# 12_LPDDR2-32_168_BGA134.net
KiCad netlist of a schematic drawn in Altium Designer
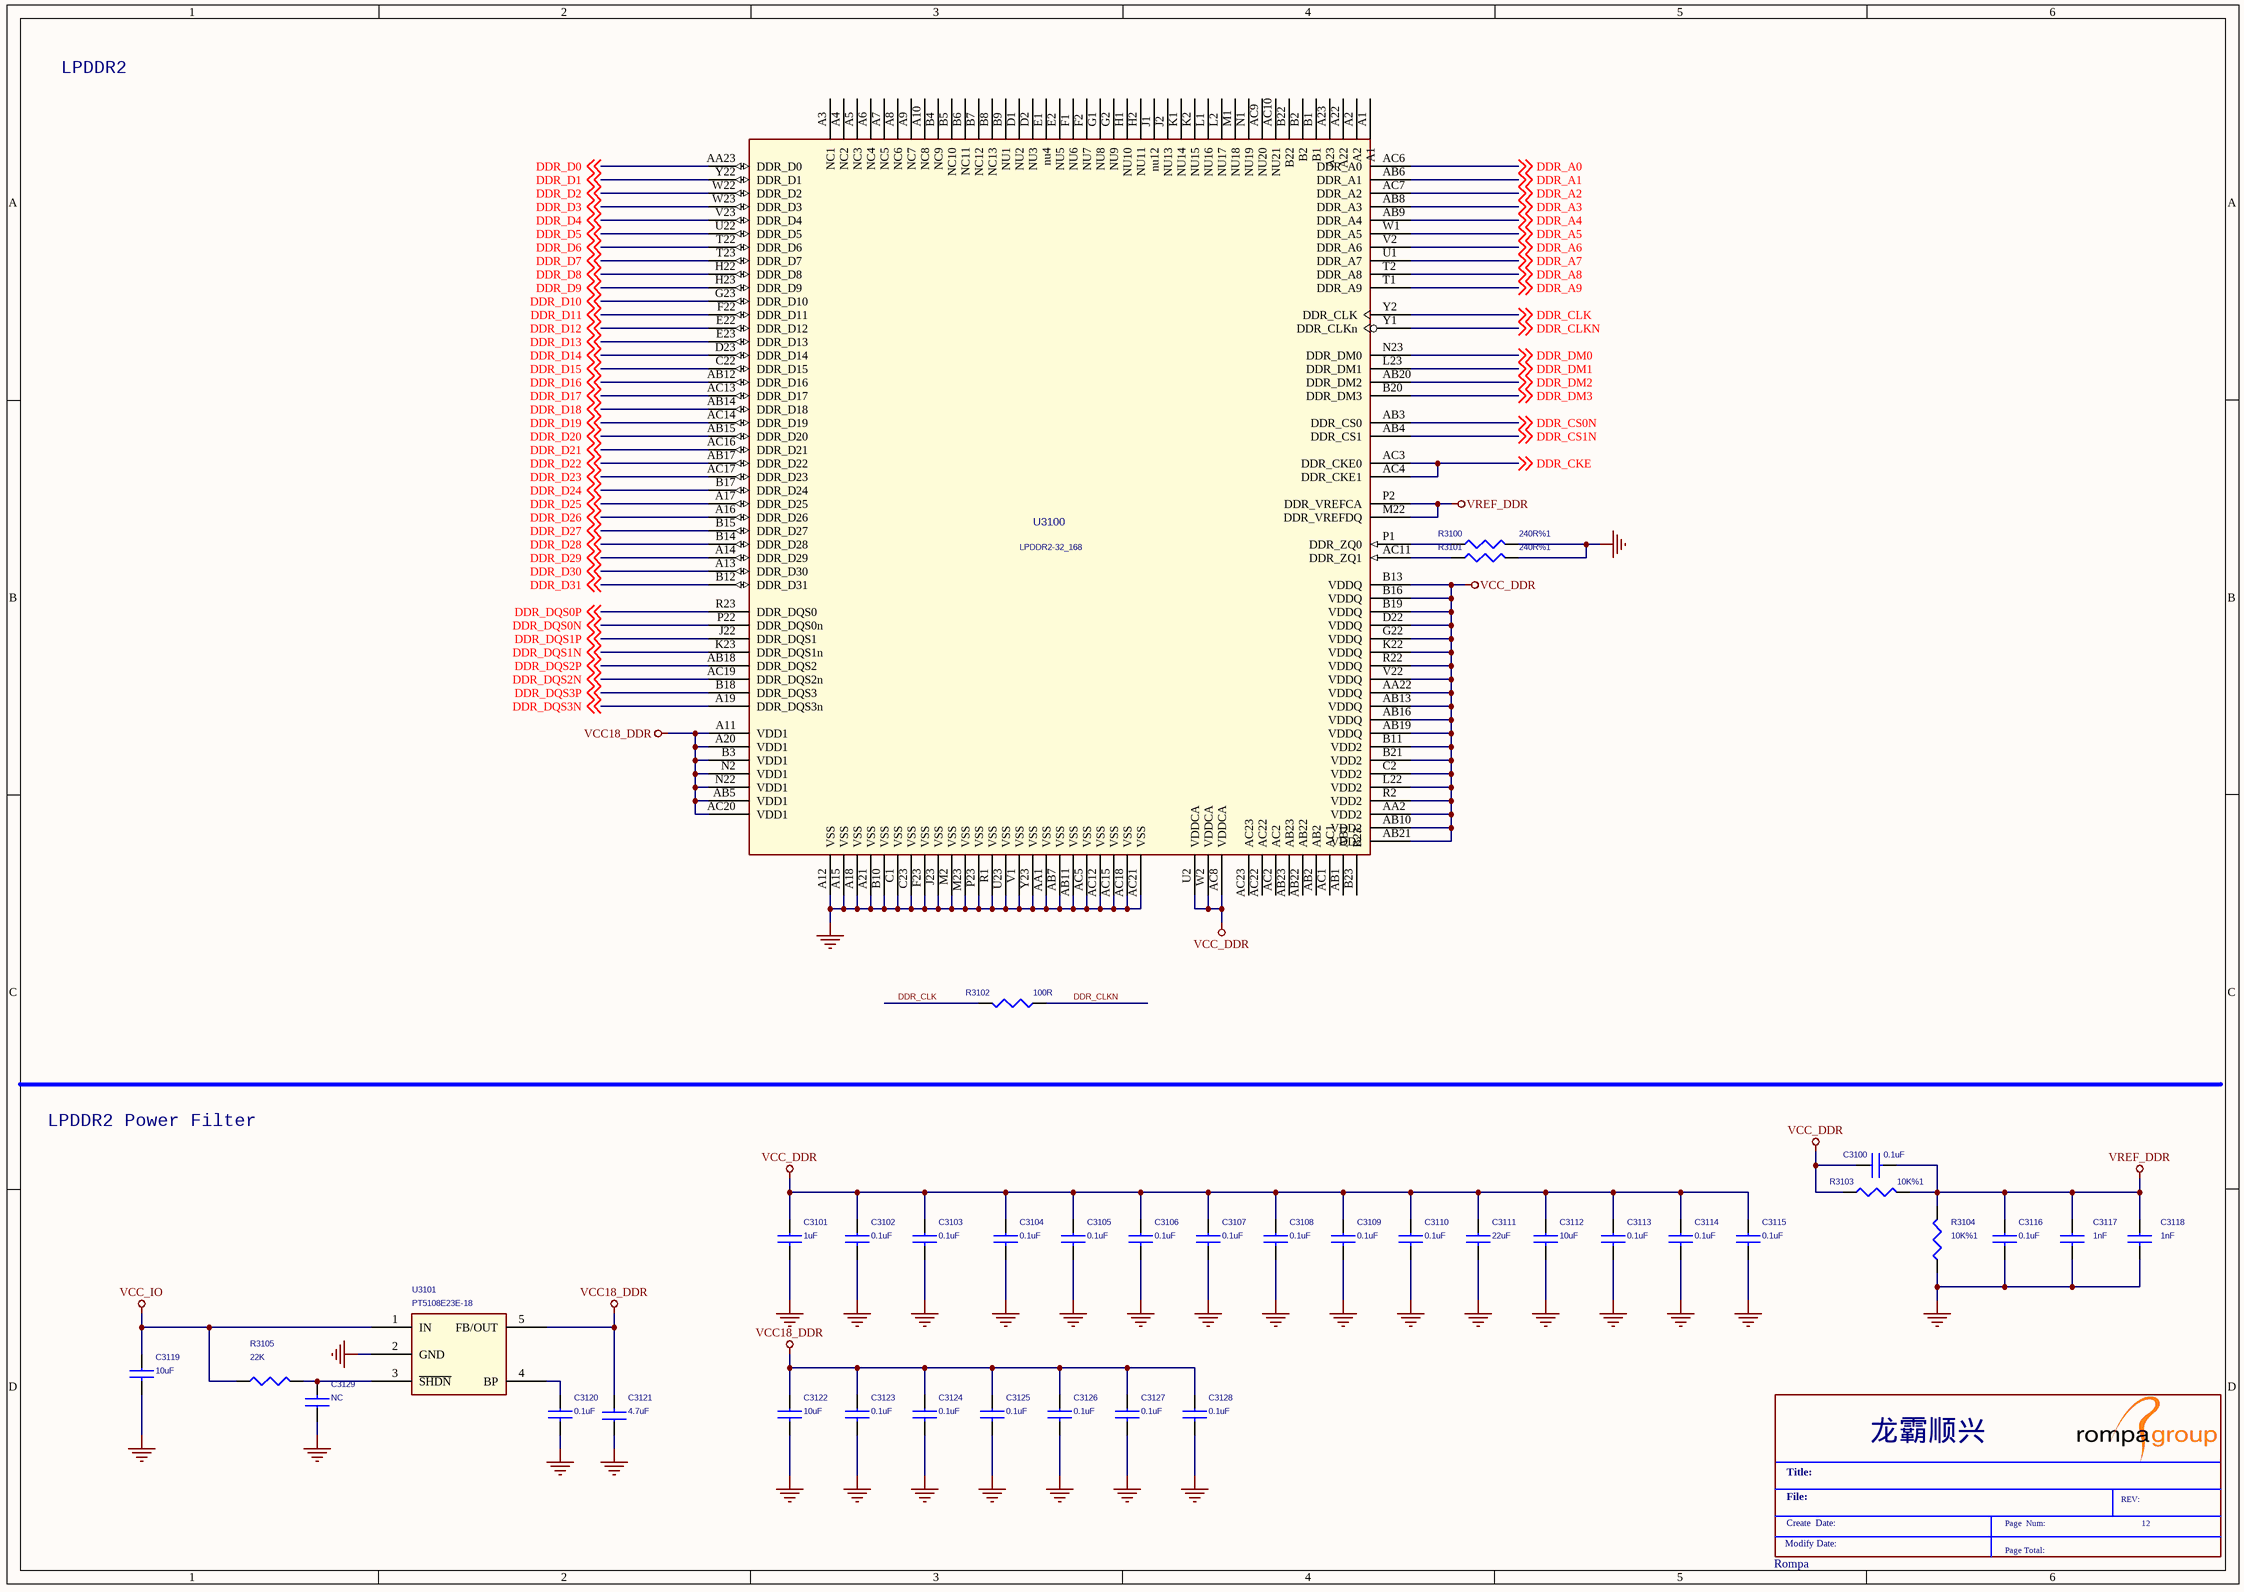
[diagram p0: 12_LPDDR2-32_168_BGA134.SchDoc]

(export (version "E")
  (design (tool "Eeschema 10.0.6"))
  (components
    (comp (ref "*")
      (value "Rompa")
      (fields (field (name "SCHEMATIC PAGE NUMBER") "12"))
      (libsource (lib "RK3128_BETA_V03_20151231_Library") (part "Rompa"))
    )
    (comp (ref "C3100") (value "0.1uF") (footprint "C0402") (libsource (lib "*") (part "CAP NP_0")))
    (comp (ref "C3101")
      (value "1uF")
      (footprint "C0402")
      (description "RoHS CHIP CAP 1uF +10/-10% X5R")
      (libsource (lib "*") (part "CAP NP"))
    )
    (comp (ref "C3102")
      (value "0.1uF")
      (footprint "C0402")
      (description "RoHS CHIP CAP 1uF +10/-10% X5R")
      (libsource (lib "*") (part "CAP NP"))
    )
    (comp (ref "C3103")
      (value "0.1uF")
      (footprint "C0402")
      (description "RoHS CHIP CAP 0.1uF +10/-10% X7R")
      (libsource (lib "*") (part "CAP NP"))
    )
    (comp (ref "C3104")
      (value "0.1uF")
      (footprint "C0402")
      (description "RoHS CHIP CAP 0.1uF +10/-10% X7R")
      (libsource (lib "*") (part "CAP NP"))
    )
    (comp (ref "C3105")
      (value "0.1uF")
      (footprint "C0402")
      (description "RoHS CHIP CAP 0.1uF +10/-10% X7R")
      (libsource (lib "*") (part "CAP NP"))
    )
    (comp (ref "C3106")
      (value "0.1uF")
      (footprint "C0402")
      (description "RoHS CHIP CAP 0.1uF +10/-10% X7R")
      (libsource (lib "*") (part "CAP NP"))
    )
    (comp (ref "C3107")
      (value "0.1uF")
      (footprint "C0402")
      (description "RoHS CHIP CAP 0.1uF +10/-10% X7R")
      (libsource (lib "*") (part "CAP NP"))
    )
    (comp (ref "C3108")
      (value "0.1uF")
      (footprint "C0402")
      (description "RoHS CHIP CAP 0.1uF +10/-10% X7R")
      (libsource (lib "*") (part "CAP NP"))
    )
    (comp (ref "C3109")
      (value "0.1uF")
      (footprint "C0402")
      (description "RoHS CHIP CAP 0.1uF +10/-10% X7R")
      (libsource (lib "*") (part "CAP NP"))
    )
    (comp (ref "C3110")
      (value "0.1uF")
      (footprint "C0402")
      (description "RoHS CHIP CAP 0.1uF +10/-10% X7R")
      (libsource (lib "*") (part "CAP NP"))
    )
    (comp (ref "C3111")
      (value "22uF")
      (footprint "C0402")
      (description "RoHS CHIP CAP 0.1uF +10/-10% X7R")
      (libsource (lib "*") (part "CAP NP"))
    )
    (comp (ref "C3112")
      (value "10uF")
      (footprint "C0402")
      (description "RoHS CHIP CAP 0.1uF +10/-10% X7R")
      (libsource (lib "*") (part "CAP NP"))
    )
    (comp (ref "C3113")
      (value "0.1uF")
      (footprint "C0402")
      (description "RoHS CHIP CAP 0.1uF +10/-10% X7R")
      (libsource (lib "*") (part "CAP NP"))
    )
    (comp (ref "C3114")
      (value "0.1uF")
      (footprint "C0402")
      (description "RoHS CHIP CAP 0.1uF +10/-10% X7R")
      (libsource (lib "*") (part "CAP NP"))
    )
    (comp (ref "C3115")
      (value "0.1uF")
      (footprint "C0402")
      (description "RoHS CHIP CAP 0.1uF +10/-10% X7R")
      (libsource (lib "*") (part "CAP NP"))
    )
    (comp (ref "C3116") (value "0.1uF") (footprint "C0402") (libsource (lib "*") (part "CAP NP_0")))
    (comp (ref "C3117") (value "1nF") (footprint "C0402") (libsource (lib "*") (part "CAP NP_0")))
    (comp (ref "C3118") (value "1nF") (footprint "C0402") (libsource (lib "*") (part "CAP NP_0")))
    (comp (ref "C3119")
      (value "10uF")
      (footprint "C0402")
      (description "CAP,MLCC,22uF,+/-10%,X5R,6.3V,SMD1206")
      (libsource (lib "*") (part "CAP NP"))
    )
    (comp (ref "C3120")
      (value "0.1uF")
      (footprint "C0402")
      (description "CAP,MLCC,100nF,+/-10%,X7R,6.3V,SMD0402")
      (libsource (lib "*") (part "CAP NP"))
    )
    (comp (ref "C3121")
      (value "4.7uF")
      (footprint "C0402")
      (description "CAP,MLCC,10uF,+/-10%,X5R,6.3V,SMD0805")
      (libsource (lib "*") (part "CAP NP"))
    )
    (comp (ref "C3122")
      (value "10uF")
      (footprint "C0402")
      (description "RoHS CHIP CAP 1uF +10/-10% X5R")
      (libsource (lib "*") (part "CAP NP"))
    )
    (comp (ref "C3123")
      (value "0.1uF")
      (footprint "C0402")
      (description "RoHS CHIP CAP 0.1uF +10/-10% X7R")
      (libsource (lib "*") (part "CAP NP"))
    )
    (comp (ref "C3124")
      (value "0.1uF")
      (footprint "C0402")
      (description "RoHS CHIP CAP 0.1uF +10/-10% X7R")
      (libsource (lib "*") (part "CAP NP"))
    )
    (comp (ref "C3125")
      (value "0.1uF")
      (footprint "C0402")
      (description "RoHS CHIP CAP 0.1uF +10/-10% X7R")
      (libsource (lib "*") (part "CAP NP"))
    )
    (comp (ref "C3126")
      (value "0.1uF")
      (footprint "C0402")
      (description "RoHS CHIP CAP 0.1uF +10/-10% X7R")
      (libsource (lib "*") (part "CAP NP"))
    )
    (comp (ref "C3127")
      (value "0.1uF")
      (footprint "C0402")
      (description "RoHS CHIP CAP 0.1uF +10/-10% X7R")
      (libsource (lib "*") (part "CAP NP"))
    )
    (comp (ref "C3128")
      (value "0.1uF")
      (footprint "C0402")
      (description "RoHS CHIP CAP 0.1uF +10/-10% X7R")
      (libsource (lib "*") (part "CAP NP"))
    )
    (comp (ref "C3129") (value "NC") (footprint "C0402") (libsource (lib "*") (part "CAP NP")))
    (comp (ref "R3100")
      (value "240R%1")
      (footprint "R0402")
      (description "贴片电阻")
      (libsource (lib "*") (part "RESISTOR_0"))
    )
    (comp (ref "R3101")
      (value "240R%1")
      (footprint "R0402")
      (description "贴片电阻")
      (libsource (lib "*") (part "RESISTOR_0"))
    )
    (comp (ref "R3102")
      (value "100R")
      (footprint "R0402")
      (description "NC/ROHS CHIP RES 100R 1/16W 5%")
      (libsource (lib "*") (part "RESISTOR"))
    )
    (comp (ref "R3103")
      (value "10K%1")
      (footprint "R0402")
      (description "贴片电阻")
      (libsource (lib "*") (part "RESISTOR_0"))
    )
    (comp (ref "R3104")
      (value "10K%1")
      (footprint "R0402")
      (description "贴片电阻")
      (libsource (lib "*") (part "RESISTOR_0"))
    )
    (comp (ref "R3105") (value "22K") (footprint "R0402") (libsource (lib "*") (part "RES 1B")))
    (comp (ref "U3100")
      (value "LPDDR2-32_168")
      (footprint "BGA134")
      (libsource (lib "*") (part "LPDDR2-32_2"))
    )
    (comp (ref "U3101")
      (value "PT5108E23E-18")
      (footprint "SOT25")
      (description "LDO,PT5108E23E-18,VINmax=5.5V,Vout=1.8V,+/-2%,500mA,SOT-23-5")
      (libsource (lib "*") (part "DS8008_4"))
    )
  )
  (nets
    (net (code "1") (name "DDR_A0") (class "Default")
      (node (ref "U3100") (pin "AC6") (pinfunction "DDR_A0_AC6") (pintype "passive"))
    )
    (net (code "2") (name "DDR_A1") (class "Default")
      (node (ref "U3100") (pin "AB6") (pinfunction "DDR_A1_AB6") (pintype "passive"))
    )
    (net (code "3") (name "DDR_A2") (class "Default")
      (node (ref "U3100") (pin "AC7") (pinfunction "DDR_A2_AC7") (pintype "passive"))
    )
    (net (code "4") (name "DDR_A3") (class "Default")
      (node (ref "U3100") (pin "AB8") (pinfunction "DDR_A3_AB8") (pintype "passive"))
    )
    (net (code "5") (name "DDR_A4") (class "Default")
      (node (ref "U3100") (pin "AB9") (pinfunction "DDR_A4_AB9") (pintype "passive"))
    )
    (net (code "6") (name "DDR_A5") (class "Default")
      (node (ref "U3100") (pin "W1") (pinfunction "DDR_A5_W1") (pintype "passive"))
    )
    (net (code "7") (name "DDR_A6") (class "Default")
      (node (ref "U3100") (pin "V2") (pinfunction "DDR_A6_V2") (pintype "passive"))
    )
    (net (code "8") (name "DDR_A7") (class "Default")
      (node (ref "U3100") (pin "U1") (pinfunction "DDR_A7_U1") (pintype "passive"))
    )
    (net (code "9") (name "DDR_A8") (class "Default")
      (node (ref "U3100") (pin "T2") (pinfunction "DDR_A8_T2") (pintype "passive"))
    )
    (net (code "10") (name "DDR_A9") (class "Default")
      (node (ref "U3100") (pin "T1") (pinfunction "DDR_A9_T1") (pintype "passive"))
    )
    (net (code "11") (name "DDR_CKE") (class "Default")
      (node (ref "U3100") (pin "AC3") (pinfunction "DDR_CKE0_AC3") (pintype "passive"))
      (node (ref "U3100") (pin "AC4") (pinfunction "DDR_CKE1_AC4") (pintype "passive"))
    )
    (net (code "12") (name "DDR_CLK") (class "Default")
      (node (ref "R3102") (pin "2") (pinfunction "2_2") (pintype "passive"))
      (node (ref "U3100") (pin "Y2") (pinfunction "DDR_CLK_Y2") (pintype "passive"))
    )
    (net (code "13") (name "DDR_CLKN") (class "Default")
      (node (ref "R3102") (pin "1") (pinfunction "1_1") (pintype "passive"))
      (node (ref "U3100") (pin "Y1") (pinfunction "DDR_CLKn_Y1") (pintype "passive"))
    )
    (net (code "14") (name "DDR_CS0N") (class "Default")
      (node (ref "U3100") (pin "AB3") (pinfunction "DDR_CS0_AB3") (pintype "passive"))
    )
    (net (code "15") (name "DDR_CS1N") (class "Default")
      (node (ref "U3100") (pin "AB4") (pinfunction "DDR_CS1_AB4") (pintype "passive"))
    )
    (net (code "16") (name "DDR_D0") (class "Default")
      (node (ref "U3100") (pin "AA23") (pinfunction "DDR_D0_AA23") (pintype "bidirectional"))
    )
    (net (code "17") (name "DDR_D1") (class "Default")
      (node (ref "U3100") (pin "Y22") (pinfunction "DDR_D1_Y22") (pintype "bidirectional"))
    )
    (net (code "18") (name "DDR_D2") (class "Default")
      (node (ref "U3100") (pin "W22") (pinfunction "DDR_D2_W22") (pintype "bidirectional"))
    )
    (net (code "19") (name "DDR_D3") (class "Default")
      (node (ref "U3100") (pin "W23") (pinfunction "DDR_D3_W23") (pintype "bidirectional"))
    )
    (net (code "20") (name "DDR_D4") (class "Default")
      (node (ref "U3100") (pin "V23") (pinfunction "DDR_D4_V23") (pintype "bidirectional"))
    )
    (net (code "21") (name "DDR_D5") (class "Default")
      (node (ref "U3100") (pin "U22") (pinfunction "DDR_D5_U22") (pintype "bidirectional"))
    )
    (net (code "22") (name "DDR_D6") (class "Default")
      (node (ref "U3100") (pin "T22") (pinfunction "DDR_D6_T22") (pintype "bidirectional"))
    )
    (net (code "23") (name "DDR_D7") (class "Default")
      (node (ref "U3100") (pin "T23") (pinfunction "DDR_D7_T23") (pintype "bidirectional"))
    )
    (net (code "24") (name "DDR_D8") (class "Default")
      (node (ref "U3100") (pin "H22") (pinfunction "DDR_D8_H22") (pintype "bidirectional"))
    )
    (net (code "25") (name "DDR_D9") (class "Default")
      (node (ref "U3100") (pin "H23") (pinfunction "DDR_D9_H23") (pintype "bidirectional"))
    )
    (net (code "26") (name "DDR_D10") (class "Default")
      (node (ref "U3100") (pin "G23") (pinfunction "DDR_D10_G23") (pintype "bidirectional"))
    )
    (net (code "27") (name "DDR_D11") (class "Default")
      (node (ref "U3100") (pin "F22") (pinfunction "DDR_D11_F22") (pintype "bidirectional"))
    )
    (net (code "28") (name "DDR_D12") (class "Default")
      (node (ref "U3100") (pin "E22") (pinfunction "DDR_D12_E22") (pintype "bidirectional"))
    )
    (net (code "29") (name "DDR_D13") (class "Default")
      (node (ref "U3100") (pin "E23") (pinfunction "DDR_D13_E23") (pintype "bidirectional"))
    )
    (net (code "30") (name "DDR_D14") (class "Default")
      (node (ref "U3100") (pin "D23") (pinfunction "DDR_D14_D23") (pintype "bidirectional"))
    )
    (net (code "31") (name "DDR_D15") (class "Default")
      (node (ref "U3100") (pin "C22") (pinfunction "DDR_D15_C22") (pintype "bidirectional"))
    )
    (net (code "32") (name "DDR_D16") (class "Default")
      (node (ref "U3100") (pin "AB12") (pinfunction "DDR_D16_AB12") (pintype "bidirectional"))
    )
    (net (code "33") (name "DDR_D17") (class "Default")
      (node (ref "U3100") (pin "AC13") (pinfunction "DDR_D17_AC13") (pintype "bidirectional"))
    )
    (net (code "34") (name "DDR_D18") (class "Default")
      (node (ref "U3100") (pin "AB14") (pinfunction "DDR_D18_AB14") (pintype "bidirectional"))
    )
    (net (code "35") (name "DDR_D19") (class "Default")
      (node (ref "U3100") (pin "AC14") (pinfunction "DDR_D19_AC14") (pintype "bidirectional"))
    )
    (net (code "36") (name "DDR_D20") (class "Default")
      (node (ref "U3100") (pin "AB15") (pinfunction "DDR_D20_AB15") (pintype "bidirectional"))
    )
    (net (code "37") (name "DDR_D21") (class "Default")
      (node (ref "U3100") (pin "AC16") (pinfunction "DDR_D21_AC16") (pintype "bidirectional"))
    )
    (net (code "38") (name "DDR_D22") (class "Default")
      (node (ref "U3100") (pin "AB17") (pinfunction "DDR_D22_AB17") (pintype "bidirectional"))
    )
    (net (code "39") (name "DDR_D23") (class "Default")
      (node (ref "U3100") (pin "AC17") (pinfunction "DDR_D23_AC17") (pintype "bidirectional"))
    )
    (net (code "40") (name "DDR_D24") (class "Default")
      (node (ref "U3100") (pin "B17") (pinfunction "DDR_D24_B17") (pintype "bidirectional"))
    )
    (net (code "41") (name "DDR_D25") (class "Default")
      (node (ref "U3100") (pin "A17") (pinfunction "DDR_D25_A17") (pintype "bidirectional"))
    )
    (net (code "42") (name "DDR_D26") (class "Default")
      (node (ref "U3100") (pin "A16") (pinfunction "DDR_D26_A16") (pintype "bidirectional"))
    )
    (net (code "43") (name "DDR_D27") (class "Default")
      (node (ref "U3100") (pin "B15") (pinfunction "DDR_D27_B15") (pintype "bidirectional"))
    )
    (net (code "44") (name "DDR_D28") (class "Default")
      (node (ref "U3100") (pin "B14") (pinfunction "DDR_D28_B14") (pintype "bidirectional"))
    )
    (net (code "45") (name "DDR_D29") (class "Default")
      (node (ref "U3100") (pin "A14") (pinfunction "DDR_D29_A14") (pintype "bidirectional"))
    )
    (net (code "46") (name "DDR_D30") (class "Default")
      (node (ref "U3100") (pin "A13") (pinfunction "DDR_D30_A13") (pintype "bidirectional"))
    )
    (net (code "47") (name "DDR_D31") (class "Default")
      (node (ref "U3100") (pin "B12") (pinfunction "DDR_D31_B12") (pintype "bidirectional"))
    )
    (net (code "48") (name "DDR_DM0") (class "Default")
      (node (ref "U3100") (pin "N23") (pinfunction "DDR_DM0_N23") (pintype "passive"))
    )
    (net (code "49") (name "DDR_DM1") (class "Default")
      (node (ref "U3100") (pin "L23") (pinfunction "DDR_DM1_L23") (pintype "passive"))
    )
    (net (code "50") (name "DDR_DM2") (class "Default")
      (node (ref "U3100") (pin "AB20") (pinfunction "DDR_DM2_AB20") (pintype "passive"))
    )
    (net (code "51") (name "DDR_DM3") (class "Default")
      (node (ref "U3100") (pin "B20") (pinfunction "DDR_DM3_B20") (pintype "passive"))
    )
    (net (code "52") (name "DDR_DQS0N") (class "Default")
      (node (ref "U3100") (pin "P22") (pinfunction "DDR_DQS0n_P22") (pintype "passive"))
    )
    (net (code "53") (name "DDR_DQS0P") (class "Default")
      (node (ref "U3100") (pin "R23") (pinfunction "DDR_DQS0_R23") (pintype "passive"))
    )
    (net (code "54") (name "DDR_DQS1N") (class "Default")
      (node (ref "U3100") (pin "K23") (pinfunction "DDR_DQS1n_K23") (pintype "passive"))
    )
    (net (code "55") (name "DDR_DQS1P") (class "Default")
      (node (ref "U3100") (pin "J22") (pinfunction "DDR_DQS1_J22") (pintype "passive"))
    )
    (net (code "56") (name "DDR_DQS2N") (class "Default")
      (node (ref "U3100") (pin "AC19") (pinfunction "DDR_DQS2n_AC19") (pintype "passive"))
    )
    (net (code "57") (name "DDR_DQS2P") (class "Default")
      (node (ref "U3100") (pin "AB18") (pinfunction "DDR_DQS2_AB18") (pintype "passive"))
    )
    (net (code "58") (name "DDR_DQS3N") (class "Default")
      (node (ref "U3100") (pin "A19") (pinfunction "DDR_DQS3n_A19") (pintype "passive"))
    )
    (net (code "59") (name "DDR_DQS3P") (class "Default")
      (node (ref "U3100") (pin "B18") (pinfunction "DDR_DQS3_B18") (pintype "passive"))
    )
    (net (code "60") (name "GND") (class "Default")
      (node (ref "C3101") (pin "2") (pinfunction "2_2") (pintype "passive"))
      (node (ref "C3102") (pin "2") (pinfunction "2_2") (pintype "passive"))
      (node (ref "C3103") (pin "2") (pinfunction "2_2") (pintype "passive"))
      (node (ref "C3104") (pin "2") (pinfunction "2_2") (pintype "passive"))
      (node (ref "C3105") (pin "2") (pinfunction "2_2") (pintype "passive"))
      (node (ref "C3106") (pin "2") (pinfunction "2_2") (pintype "passive"))
      (node (ref "C3107") (pin "2") (pinfunction "2_2") (pintype "passive"))
      (node (ref "C3108") (pin "2") (pinfunction "2_2") (pintype "passive"))
      (node (ref "C3109") (pin "2") (pinfunction "2_2") (pintype "passive"))
      (node (ref "C3110") (pin "2") (pinfunction "2_2") (pintype "passive"))
      (node (ref "C3111") (pin "2") (pinfunction "2_2") (pintype "passive"))
      (node (ref "C3112") (pin "2") (pinfunction "2_2") (pintype "passive"))
      (node (ref "C3113") (pin "2") (pinfunction "2_2") (pintype "passive"))
      (node (ref "C3114") (pin "2") (pinfunction "2_2") (pintype "passive"))
      (node (ref "C3115") (pin "2") (pinfunction "2_2") (pintype "passive"))
      (node (ref "C3116") (pin "2") (pinfunction "2_2") (pintype "passive"))
      (node (ref "C3117") (pin "2") (pinfunction "2_2") (pintype "passive"))
      (node (ref "C3118") (pin "2") (pinfunction "2_2") (pintype "passive"))
      (node (ref "C3119") (pin "2") (pinfunction "2_2") (pintype "passive"))
      (node (ref "C3120") (pin "2") (pinfunction "2_2") (pintype "passive"))
      (node (ref "C3121") (pin "1") (pinfunction "1_1") (pintype "passive"))
      (node (ref "C3122") (pin "2") (pinfunction "2_2") (pintype "passive"))
      (node (ref "C3123") (pin "2") (pinfunction "2_2") (pintype "passive"))
      (node (ref "C3124") (pin "2") (pinfunction "2_2") (pintype "passive"))
      (node (ref "C3125") (pin "2") (pinfunction "2_2") (pintype "passive"))
      (node (ref "C3126") (pin "2") (pinfunction "2_2") (pintype "passive"))
      (node (ref "C3127") (pin "2") (pinfunction "2_2") (pintype "passive"))
      (node (ref "C3128") (pin "2") (pinfunction "2_2") (pintype "passive"))
      (node (ref "C3129") (pin "1") (pinfunction "1_1") (pintype "passive"))
      (node (ref "R3100") (pin "2") (pinfunction "2_2") (pintype "passive"))
      (node (ref "R3101") (pin "2") (pinfunction "2_2") (pintype "passive"))
      (node (ref "R3104") (pin "1") (pinfunction "1_1") (pintype "passive"))
      (node (ref "U3100") (pin "A12") (pinfunction "VSS_A12") (pintype "power_in"))
      (node (ref "U3100") (pin "A15") (pinfunction "VSS_A15") (pintype "power_in"))
      (node (ref "U3100") (pin "A18") (pinfunction "VSS_A18") (pintype "power_in"))
      (node (ref "U3100") (pin "A21") (pinfunction "VSS_A21") (pintype "power_in"))
      (node (ref "U3100") (pin "AA1") (pinfunction "VSS_AA1") (pintype "power_in"))
      (node (ref "U3100") (pin "AB11") (pinfunction "VSS_AB11") (pintype "power_in"))
      (node (ref "U3100") (pin "AB7") (pinfunction "VSS_AB7") (pintype "power_in"))
      (node (ref "U3100") (pin "AC12") (pinfunction "VSS_AC12") (pintype "power_in"))
      (node (ref "U3100") (pin "AC15") (pinfunction "VSS_AC15") (pintype "power_in"))
      (node (ref "U3100") (pin "AC18") (pinfunction "VSS_AC18") (pintype "power_in"))
      (node (ref "U3100") (pin "AC21") (pinfunction "VSS_AC21") (pintype "power_in"))
      (node (ref "U3100") (pin "AC5") (pinfunction "VSS_AC5") (pintype "power_in"))
      (node (ref "U3100") (pin "B10") (pinfunction "VSS_B10") (pintype "power_in"))
      (node (ref "U3100") (pin "C1") (pinfunction "VSS_C1") (pintype "power_in"))
      (node (ref "U3100") (pin "C23") (pinfunction "VSS_C23") (pintype "power_in"))
      (node (ref "U3100") (pin "F23") (pinfunction "VSS_F23") (pintype "power_in"))
      (node (ref "U3100") (pin "J23") (pinfunction "VSS_J23") (pintype "power_in"))
      (node (ref "U3100") (pin "M2") (pinfunction "VSS_M2") (pintype "power_in"))
      (node (ref "U3100") (pin "M23") (pinfunction "VSS_M23") (pintype "power_in"))
      (node (ref "U3100") (pin "P23") (pinfunction "VSS_P23") (pintype "power_in"))
      (node (ref "U3100") (pin "R1") (pinfunction "VSS_R1") (pintype "power_in"))
      (node (ref "U3100") (pin "U23") (pinfunction "VSS_U23") (pintype "power_in"))
      (node (ref "U3100") (pin "V1") (pinfunction "VSS_V1") (pintype "power_in"))
      (node (ref "U3100") (pin "Y23") (pinfunction "VSS_Y23") (pintype "power_in"))
      (node (ref "U3101") (pin "2") (pinfunction "GND_2") (pintype "passive"))
    )
    (net (code "61") (name "Net-(U3100-DDR_ZQ0)") (class "Default")
      (node (ref "R3100") (pin "1") (pinfunction "1_1") (pintype "passive"))
      (node (ref "U3100") (pin "P1") (pinfunction "DDR_ZQ0_P1") (pintype "input"))
    )
    (net (code "62") (name "Net-(U3100-DDR_ZQ1)") (class "Default")
      (node (ref "R3101") (pin "1") (pinfunction "1_1") (pintype "passive"))
      (node (ref "U3100") (pin "AC11") (pinfunction "DDR_ZQ1_AC11") (pintype "input"))
    )
    (net (code "63") (name "Net-(U3101-BP)") (class "Default")
      (node (ref "C3120") (pin "1") (pinfunction "1_1") (pintype "passive"))
      (node (ref "U3101") (pin "4") (pinfunction "BP_4") (pintype "passive"))
    )
    (net (code "64") (name "Net-(U3101-~{SHDN})") (class "Default")
      (node (ref "C3129") (pin "2") (pinfunction "2_2") (pintype "passive"))
      (node (ref "R3105") (pin "2") (pinfunction "2_2") (pintype "passive"))
      (node (ref "U3101") (pin "3") (pinfunction "~{SHDN}_3") (pintype "passive"))
    )
    (net (code "65") (name "VCC18_DDR") (class "Default")
      (node (ref "C3121") (pin "2") (pinfunction "2_2") (pintype "passive"))
      (node (ref "C3122") (pin "1") (pinfunction "1_1") (pintype "passive"))
      (node (ref "C3123") (pin "1") (pinfunction "1_1") (pintype "passive"))
      (node (ref "C3124") (pin "1") (pinfunction "1_1") (pintype "passive"))
      (node (ref "C3125") (pin "1") (pinfunction "1_1") (pintype "passive"))
      (node (ref "C3126") (pin "1") (pinfunction "1_1") (pintype "passive"))
      (node (ref "C3127") (pin "1") (pinfunction "1_1") (pintype "passive"))
      (node (ref "C3128") (pin "1") (pinfunction "1_1") (pintype "passive"))
      (node (ref "U3100") (pin "A11") (pinfunction "VDD1_A11") (pintype "power_in"))
      (node (ref "U3100") (pin "A20") (pinfunction "VDD1_A20") (pintype "power_in"))
      (node (ref "U3100") (pin "AB5") (pinfunction "VDD1_AB5") (pintype "power_in"))
      (node (ref "U3100") (pin "AC20") (pinfunction "VDD1_AC20") (pintype "power_in"))
      (node (ref "U3100") (pin "B3") (pinfunction "VDD1_B3") (pintype "power_in"))
      (node (ref "U3100") (pin "N2") (pinfunction "VDD1_N2") (pintype "power_in"))
      (node (ref "U3100") (pin "N22") (pinfunction "VDD1_N22") (pintype "power_in"))
      (node (ref "U3101") (pin "5") (pinfunction "FB/OUT_5") (pintype "passive"))
    )
    (net (code "66") (name "VCC_DDR") (class "Default")
      (node (ref "C3100") (pin "1") (pinfunction "1_1") (pintype "passive"))
      (node (ref "C3101") (pin "1") (pinfunction "1_1") (pintype "passive"))
      (node (ref "C3102") (pin "1") (pinfunction "1_1") (pintype "passive"))
      (node (ref "C3103") (pin "1") (pinfunction "1_1") (pintype "passive"))
      (node (ref "C3104") (pin "1") (pinfunction "1_1") (pintype "passive"))
      (node (ref "C3105") (pin "1") (pinfunction "1_1") (pintype "passive"))
      (node (ref "C3106") (pin "1") (pinfunction "1_1") (pintype "passive"))
      (node (ref "C3107") (pin "1") (pinfunction "1_1") (pintype "passive"))
      (node (ref "C3108") (pin "1") (pinfunction "1_1") (pintype "passive"))
      (node (ref "C3109") (pin "1") (pinfunction "1_1") (pintype "passive"))
      (node (ref "C3110") (pin "1") (pinfunction "1_1") (pintype "passive"))
      (node (ref "C3111") (pin "1") (pinfunction "1_1") (pintype "passive"))
      (node (ref "C3112") (pin "1") (pinfunction "1_1") (pintype "passive"))
      (node (ref "C3113") (pin "1") (pinfunction "1_1") (pintype "passive"))
      (node (ref "C3114") (pin "1") (pinfunction "1_1") (pintype "passive"))
      (node (ref "C3115") (pin "1") (pinfunction "1_1") (pintype "passive"))
      (node (ref "R3103") (pin "1") (pinfunction "1_1") (pintype "passive"))
      (node (ref "U3100") (pin "AA2") (pinfunction "VDD2_AA2") (pintype "power_in"))
      (node (ref "U3100") (pin "AA22") (pinfunction "VDDQ_AA22") (pintype "power_in"))
      (node (ref "U3100") (pin "AB10") (pinfunction "VDD2_AB10") (pintype "power_in"))
      (node (ref "U3100") (pin "AB13") (pinfunction "VDDQ_AB13") (pintype "power_in"))
      (node (ref "U3100") (pin "AB16") (pinfunction "VDDQ_AB16") (pintype "power_in"))
      (node (ref "U3100") (pin "AB19") (pinfunction "VDDQ_AB19") (pintype "power_in"))
      (node (ref "U3100") (pin "AB21") (pinfunction "VDD2_AB21") (pintype "power_in"))
      (node (ref "U3100") (pin "AC8") (pinfunction "VDDCA_AC8") (pintype "power_in"))
      (node (ref "U3100") (pin "B11") (pinfunction "VDD2_B11") (pintype "power_in"))
      (node (ref "U3100") (pin "B13") (pinfunction "VDDQ_B13") (pintype "power_in"))
      (node (ref "U3100") (pin "B16") (pinfunction "VDDQ_B16") (pintype "power_in"))
      (node (ref "U3100") (pin "B19") (pinfunction "VDDQ_B19") (pintype "power_in"))
      (node (ref "U3100") (pin "B21") (pinfunction "VDD2_B21") (pintype "power_in"))
      (node (ref "U3100") (pin "C2") (pinfunction "VDD2_C2") (pintype "power_in"))
      (node (ref "U3100") (pin "D22") (pinfunction "VDDQ_D22") (pintype "power_in"))
      (node (ref "U3100") (pin "G22") (pinfunction "VDDQ_G22") (pintype "power_in"))
      (node (ref "U3100") (pin "K22") (pinfunction "VDDQ_K22") (pintype "power_in"))
      (node (ref "U3100") (pin "L22") (pinfunction "VDD2_L22") (pintype "power_in"))
      (node (ref "U3100") (pin "R2") (pinfunction "VDD2_R2") (pintype "power_in"))
      (node (ref "U3100") (pin "R22") (pinfunction "VDDQ_R22") (pintype "power_in"))
      (node (ref "U3100") (pin "U2") (pinfunction "VDDCA_U2") (pintype "power_in"))
      (node (ref "U3100") (pin "V22") (pinfunction "VDDQ_V22") (pintype "power_in"))
      (node (ref "U3100") (pin "W2") (pinfunction "VDDCA_W2") (pintype "power_in"))
    )
    (net (code "67") (name "VCC_IO") (class "Default")
      (node (ref "C3119") (pin "1") (pinfunction "1_1") (pintype "passive"))
      (node (ref "R3105") (pin "1") (pinfunction "1_1") (pintype "passive"))
      (node (ref "U3101") (pin "1") (pinfunction "IN_1") (pintype "passive"))
    )
    (net (code "68") (name "VREF_DDR") (class "Default")
      (node (ref "C3100") (pin "2") (pinfunction "2_2") (pintype "passive"))
      (node (ref "C3116") (pin "1") (pinfunction "1_1") (pintype "passive"))
      (node (ref "C3117") (pin "1") (pinfunction "1_1") (pintype "passive"))
      (node (ref "C3118") (pin "1") (pinfunction "1_1") (pintype "passive"))
      (node (ref "R3103") (pin "2") (pinfunction "2_2") (pintype "passive"))
      (node (ref "R3104") (pin "2") (pinfunction "2_2") (pintype "passive"))
      (node (ref "U3100") (pin "M22") (pinfunction "DDR_VREFDQ_M22") (pintype "power_in"))
      (node (ref "U3100") (pin "P2") (pinfunction "DDR_VREFCA_P2") (pintype "passive"))
    )
    (net (code "69") (name "unconnected-(U3100-NC1-PadA3)") (class "Default")
      (node (ref "U3100") (pin "A3") (pinfunction "NC1_A3") (pintype "passive"))
    )
    (net (code "70") (name "unconnected-(U3100-NC2-PadA4)") (class "Default")
      (node (ref "U3100") (pin "A4") (pinfunction "NC2_A4") (pintype "passive"))
    )
    (net (code "71") (name "unconnected-(U3100-NC3-PadA5)") (class "Default")
      (node (ref "U3100") (pin "A5") (pinfunction "NC3_A5") (pintype "passive"))
    )
    (net (code "72") (name "unconnected-(U3100-NC4-PadA6)") (class "Default")
      (node (ref "U3100") (pin "A6") (pinfunction "NC4_A6") (pintype "passive"))
    )
    (net (code "73") (name "unconnected-(U3100-NC5-PadA7)") (class "Default")
      (node (ref "U3100") (pin "A7") (pinfunction "NC5_A7") (pintype "passive"))
    )
    (net (code "74") (name "unconnected-(U3100-NC6-PadA8)") (class "Default")
      (node (ref "U3100") (pin "A8") (pinfunction "NC6_A8") (pintype "passive"))
    )
    (net (code "75") (name "unconnected-(U3100-NC7-PadA9)") (class "Default")
      (node (ref "U3100") (pin "A9") (pinfunction "NC7_A9") (pintype "passive"))
    )
    (net (code "76") (name "unconnected-(U3100-NC8-PadA10)") (class "Default")
      (node (ref "U3100") (pin "A10") (pinfunction "NC8_A10") (pintype "passive"))
    )
    (net (code "77") (name "unconnected-(U3100-NC9-PadB4)") (class "Default")
      (node (ref "U3100") (pin "B4") (pinfunction "NC9_B4") (pintype "passive"))
    )
    (net (code "78") (name "unconnected-(U3100-NC10-PadB5)") (class "Default")
      (node (ref "U3100") (pin "B5") (pinfunction "NC10_B5") (pintype "passive"))
    )
    (net (code "79") (name "unconnected-(U3100-NC11-PadB6)") (class "Default")
      (node (ref "U3100") (pin "B6") (pinfunction "NC11_B6") (pintype "passive"))
    )
    (net (code "80") (name "unconnected-(U3100-NC12-PadB7)") (class "Default")
      (node (ref "U3100") (pin "B7") (pinfunction "NC12_B7") (pintype "passive"))
    )
    (net (code "81") (name "unconnected-(U3100-NC13-PadB8)") (class "Default")
      (node (ref "U3100") (pin "B8") (pinfunction "NC13_B8") (pintype "passive"))
    )
    (net (code "82") (name "unconnected-(U3100-NU1-PadB9)") (class "Default")
      (node (ref "U3100") (pin "B9") (pinfunction "NU1_B9") (pintype "passive"))
    )
    (net (code "83") (name "unconnected-(U3100-NU2-PadD1)") (class "Default")
      (node (ref "U3100") (pin "D1") (pinfunction "NU2_D1") (pintype "passive"))
    )
    (net (code "84") (name "unconnected-(U3100-NU3-PadD2)") (class "Default")
      (node (ref "U3100") (pin "D2") (pinfunction "NU3_D2") (pintype "passive"))
    )
    (net (code "85") (name "unconnected-(U3100-NU5-PadE2)") (class "Default")
      (node (ref "U3100") (pin "E2") (pinfunction "NU5_E2") (pintype "passive"))
    )
    (net (code "86") (name "unconnected-(U3100-NU6-PadF1)") (class "Default")
      (node (ref "U3100") (pin "F1") (pinfunction "NU6_F1") (pintype "passive"))
    )
    (net (code "87") (name "unconnected-(U3100-NU7-PadF2)") (class "Default")
      (node (ref "U3100") (pin "F2") (pinfunction "NU7_F2") (pintype "passive"))
    )
    (net (code "88") (name "unconnected-(U3100-NU8-PadG1)") (class "Default")
      (node (ref "U3100") (pin "G1") (pinfunction "NU8_G1") (pintype "passive"))
    )
    (net (code "89") (name "unconnected-(U3100-NU9-PadG2)") (class "Default")
      (node (ref "U3100") (pin "G2") (pinfunction "NU9_G2") (pintype "passive"))
    )
    (net (code "90") (name "unconnected-(U3100-NU10-PadH1)") (class "Default")
      (node (ref "U3100") (pin "H1") (pinfunction "NU10_H1") (pintype "passive"))
    )
    (net (code "91") (name "unconnected-(U3100-NU11-PadH2)") (class "Default")
      (node (ref "U3100") (pin "H2") (pinfunction "NU11_H2") (pintype "passive"))
    )
    (net (code "92") (name "unconnected-(U3100-NU13-PadJ2)") (class "Default")
      (node (ref "U3100") (pin "J2") (pinfunction "NU13_J2") (pintype "passive"))
    )
    (net (code "93") (name "unconnected-(U3100-NU14-PadK1)") (class "Default")
      (node (ref "U3100") (pin "K1") (pinfunction "NU14_K1") (pintype "passive"))
    )
    (net (code "94") (name "unconnected-(U3100-NU15-PadK2)") (class "Default")
      (node (ref "U3100") (pin "K2") (pinfunction "NU15_K2") (pintype "passive"))
    )
    (net (code "95") (name "unconnected-(U3100-NU16-PadL1)") (class "Default")
      (node (ref "U3100") (pin "L1") (pinfunction "NU16_L1") (pintype "passive"))
    )
    (net (code "96") (name "unconnected-(U3100-NU17-PadL2)") (class "Default")
      (node (ref "U3100") (pin "L2") (pinfunction "NU17_L2") (pintype "passive"))
    )
    (net (code "97") (name "unconnected-(U3100-NU18-PadM1)") (class "Default")
      (node (ref "U3100") (pin "M1") (pinfunction "NU18_M1") (pintype "passive"))
    )
    (net (code "98") (name "unconnected-(U3100-NU19-PadN1)") (class "Default")
      (node (ref "U3100") (pin "N1") (pinfunction "NU19_N1") (pintype "passive"))
    )
    (net (code "99") (name "unconnected-(U3100-NU20-PadAC9)") (class "Default")
      (node (ref "U3100") (pin "AC9") (pinfunction "NU20_AC9") (pintype "passive"))
    )
    (net (code "100") (name "unconnected-(U3100-NU21-PadAC10)") (class "Default")
      (node (ref "U3100") (pin "AC10") (pinfunction "NU21_AC10") (pintype "passive"))
    )
    (net (code "101") (name "unconnected-(U3100-PadA1)") (class "Default")
      (node (ref "U3100") (pin "A1") (pinfunction "A1_A1") (pintype "passive"))
    )
    (net (code "102") (name "unconnected-(U3100-PadA2)") (class "Default")
      (node (ref "U3100") (pin "A2") (pinfunction "A2_A2") (pintype "passive"))
    )
    (net (code "103") (name "unconnected-(U3100-PadA22)") (class "Default")
      (node (ref "U3100") (pin "A22") (pinfunction "A22_A22") (pintype "passive"))
    )
    (net (code "104") (name "unconnected-(U3100-PadA23)") (class "Default")
      (node (ref "U3100") (pin "A23") (pinfunction "A23_A23") (pintype "passive"))
    )
    (net (code "105") (name "unconnected-(U3100-PadAB1)") (class "Default")
      (node (ref "U3100") (pin "AB1") (pinfunction "AB1_AB1") (pintype "power_in"))
    )
    (net (code "106") (name "unconnected-(U3100-PadAB2)") (class "Default")
      (node (ref "U3100") (pin "AB2") (pinfunction "AB2_AB2") (pintype "power_in"))
    )
    (net (code "107") (name "unconnected-(U3100-PadAB22)") (class "Default")
      (node (ref "U3100") (pin "AB22") (pinfunction "AB22_AB22") (pintype "power_in"))
    )
    (net (code "108") (name "unconnected-(U3100-PadAB23)") (class "Default")
      (node (ref "U3100") (pin "AB23") (pinfunction "AB23_AB23") (pintype "power_in"))
    )
    (net (code "109") (name "unconnected-(U3100-PadAC1)") (class "Default")
      (node (ref "U3100") (pin "AC1") (pinfunction "AC1_AC1") (pintype "power_in"))
    )
    (net (code "110") (name "unconnected-(U3100-PadAC2)") (class "Default")
      (node (ref "U3100") (pin "AC2") (pinfunction "AC2_AC2") (pintype "power_in"))
    )
    (net (code "111") (name "unconnected-(U3100-PadAC22)") (class "Default")
      (node (ref "U3100") (pin "AC22") (pinfunction "AC22_AC22") (pintype "power_in"))
    )
    (net (code "112") (name "unconnected-(U3100-PadAC23)") (class "Default")
      (node (ref "U3100") (pin "AC23") (pinfunction "AC23_AC23") (pintype "power_in"))
    )
    (net (code "113") (name "unconnected-(U3100-PadB1)") (class "Default")
      (node (ref "U3100") (pin "B1") (pinfunction "B1_B1") (pintype "passive"))
    )
    (net (code "114") (name "unconnected-(U3100-PadB2)") (class "Default")
      (node (ref "U3100") (pin "B2") (pinfunction "B2_B2") (pintype "passive"))
    )
    (net (code "115") (name "unconnected-(U3100-PadB22)") (class "Default")
      (node (ref "U3100") (pin "B22") (pinfunction "B22_B22") (pintype "passive"))
    )
    (net (code "116") (name "unconnected-(U3100-PadB23)") (class "Default")
      (node (ref "U3100") (pin "B23") (pinfunction "B23_B23") (pintype "power_in"))
    )
    (net (code "117") (name "unconnected-(U3100-nu4-PadE1)") (class "Default")
      (node (ref "U3100") (pin "E1") (pinfunction "nu4_E1") (pintype "passive"))
    )
    (net (code "118") (name "unconnected-(U3100-nu12-PadJ1)") (class "Default")
      (node (ref "U3100") (pin "J1") (pinfunction "nu12_J1") (pintype "passive"))
    )
  )
)
